# InertiaScreen_CurriculumDesign.net
KiCad netlist of a schematic drawn in Altium Designer
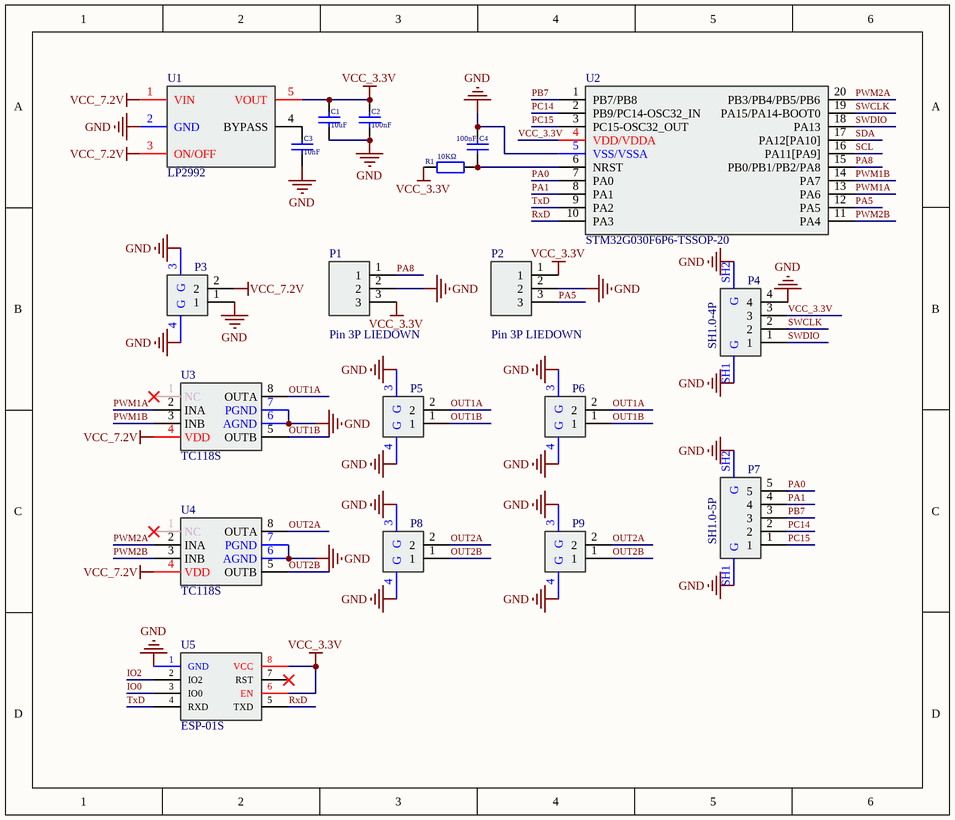
[diagram p0: InertiaScreen_CurriculumDesign.SchDoc]

(export (version "E")
  (design (tool "Eeschema 10.0.6"))
  (components
    (comp (ref "C1")
      (value "10uF")
      (footprint "0402_C")
      (description "贴片电容")
      (libsource (lib "Miscellaneous Devices LC") (part "0402 10uF (106) 20% 6.3V"))
    )
    (comp (ref "C2")
      (value "100nF")
      (footprint "0402_C")
      (description "贴片电容")
      (libsource (lib "Miscellaneous Devices LC") (part "0402 100nF (104) 10% 16V"))
    )
    (comp (ref "C3")
      (value "10nF")
      (footprint "0402_C")
      (description "贴片电容")
      (libsource (lib "Miscellaneous Devices LC") (part "0402 10nF (103) 10% 50V"))
    )
    (comp (ref "C4")
      (value "100nF")
      (footprint "0402_C")
      (description "贴片电容")
      (libsource (lib "Miscellaneous Devices LC") (part "0402 100nF (104) 10% 16V"))
    )
    (comp (ref "P1")
      (value "Pin 3P LIEDOWN")
      (footprint "Pin 3P LieDown")
      (description "排针卧贴 3P")
      (libsource (lib "IntegratedDevices") (part "Pin 3P LIEDOWN"))
    )
    (comp (ref "P2")
      (value "Pin 3P LIEDOWN")
      (footprint "Pin 3P LieDown")
      (description "排针卧贴 3P")
      (libsource (lib "IntegratedDevices") (part "Pin 3P LIEDOWN"))
    )
    (comp (ref "P3")
      (value "SH1.00mm 2P")
      (footprint "SH1.0-2P")
      (description "SH1.00mm 2P 卧贴")
      (libsource (lib "IntegratedDevices") (part "SH1.00mm 2P"))
    )
    (comp (ref "P4")
      (value "SH1.0-4P")
      (footprint "SH1.0-4P")
      (description "SH1.00mm 4P 卧贴")
      (libsource (lib "IntegratedDevices") (part "SH1.0-4P"))
    )
    (comp (ref "P5")
      (value "SH1.00mm 2P")
      (footprint "SH1.0-2P")
      (description "SH1.00mm 2P 卧贴")
      (libsource (lib "IntegratedDevices") (part "SH1.00mm 2P"))
    )
    (comp (ref "P6")
      (value "SH1.00mm 2P")
      (footprint "SH1.0-2P")
      (description "SH1.00mm 2P 卧贴")
      (libsource (lib "IntegratedDevices") (part "SH1.00mm 2P"))
    )
    (comp (ref "P7")
      (value "SH1.0-5P")
      (footprint "SH1.0-5P")
      (description "SH1.00mm 5P 卧贴")
      (libsource (lib "IntegratedDevices") (part "SH1.0-5P"))
    )
    (comp (ref "P8")
      (value "SH1.00mm 2P")
      (footprint "SH1.0-2P")
      (description "SH1.00mm 2P 卧贴")
      (libsource (lib "IntegratedDevices") (part "SH1.00mm 2P"))
    )
    (comp (ref "P9")
      (value "SH1.00mm 2P")
      (footprint "SH1.0-2P")
      (description "SH1.00mm 2P 卧贴")
      (libsource (lib "IntegratedDevices") (part "SH1.00mm 2P"))
    )
    (comp (ref "R1")
      (value "10KΩ")
      (footprint "0402_R")
      (description "贴片电阻")
      (libsource (lib "Miscellaneous Devices LC") (part "0402 10KΩ (1002) 1%"))
    )
    (comp (ref "U1")
      (value "LP2992")
      (footprint "SOT23-5")
      (description "LDO 5.x-3.3V")
      (libsource (lib "IntegratedDevices") (part "LP2992"))
    )
    (comp (ref "U2")
      (value "STM32G030F6P6-TSSOP-20")
      (footprint "TSSOP-20")
      (libsource (lib "IntegratedDevices") (part "STM32G030F6P6-TSSOP-20"))
    )
    (comp (ref "U3")
      (value "TC118S")
      (footprint "SOP-8")
      (description "TC118S FM单路直流电机驱动")
      (libsource (lib "IntegratedDevices") (part "TC118S"))
    )
    (comp (ref "U4")
      (value "TC118S")
      (footprint "SOP-8")
      (description "TC118S FM单路直流电机驱动")
      (libsource (lib "IntegratedDevices") (part "TC118S"))
    )
    (comp (ref "U5")
      (value "ESP-01S")
      (footprint "ESP-01S-NoSlik")
      (description "ESP01S开发板")
      (libsource (lib "IntegratedDevices") (part "ESP-01S"))
    )
  )
  (nets
    (net (code "1") (name "/IO0") (class "Default")
      (node (ref "U5") (pin "3") (pinfunction "IO0_3") (pintype "passive"))
    )
    (net (code "2") (name "/IO2") (class "Default")
      (node (ref "U5") (pin "2") (pinfunction "IO2_2") (pintype "passive"))
    )
    (net (code "3") (name "/OUT1A") (class "Default")
      (node (ref "P5") (pin "2") (pinfunction "2_2") (pintype "passive"))
      (node (ref "P6") (pin "2") (pinfunction "2_2") (pintype "passive"))
      (node (ref "U3") (pin "8") (pinfunction "OUTA_8") (pintype "passive"))
    )
    (net (code "4") (name "/OUT1B") (class "Default")
      (node (ref "P5") (pin "1") (pinfunction "1_1") (pintype "passive"))
      (node (ref "P6") (pin "1") (pinfunction "1_1") (pintype "passive"))
      (node (ref "U3") (pin "5") (pinfunction "OUTB_5") (pintype "passive"))
    )
    (net (code "5") (name "/OUT2A") (class "Default")
      (node (ref "P8") (pin "2") (pinfunction "2_2") (pintype "passive"))
      (node (ref "P9") (pin "2") (pinfunction "2_2") (pintype "passive"))
      (node (ref "U4") (pin "8") (pinfunction "OUTA_8") (pintype "passive"))
    )
    (net (code "6") (name "/OUT2B") (class "Default")
      (node (ref "P8") (pin "1") (pinfunction "1_1") (pintype "passive"))
      (node (ref "P9") (pin "1") (pinfunction "1_1") (pintype "passive"))
      (node (ref "U4") (pin "5") (pinfunction "OUTB_5") (pintype "passive"))
    )
    (net (code "7") (name "/PA0") (class "Default")
      (node (ref "P7") (pin "5") (pinfunction "5_5") (pintype "passive"))
      (node (ref "U2") (pin "7") (pinfunction "PA0_7") (pintype "passive"))
    )
    (net (code "8") (name "/PA1") (class "Default")
      (node (ref "P7") (pin "4") (pinfunction "4_4") (pintype "passive"))
      (node (ref "U2") (pin "8") (pinfunction "PA1_8") (pintype "passive"))
    )
    (net (code "9") (name "/PA5") (class "Default")
      (node (ref "P2") (pin "3") (pinfunction "3_3") (pintype "passive"))
      (node (ref "U2") (pin "12") (pinfunction "PA5_12") (pintype "passive"))
    )
    (net (code "10") (name "/PA8") (class "Default")
      (node (ref "P1") (pin "1") (pinfunction "1_1") (pintype "passive"))
      (node (ref "U2") (pin "15") (pinfunction "PB0/PB1/PB2/PA8_15") (pintype "passive"))
    )
    (net (code "11") (name "/PB7") (class "Default")
      (node (ref "P7") (pin "3") (pinfunction "3_3") (pintype "passive"))
      (node (ref "U2") (pin "1") (pinfunction "PB7/PB8_1") (pintype "passive"))
    )
    (net (code "12") (name "/PC14") (class "Default")
      (node (ref "P7") (pin "2") (pinfunction "2_2") (pintype "passive"))
      (node (ref "U2") (pin "2") (pinfunction "PB9/PC14-OSC32_IN_2") (pintype "passive"))
    )
    (net (code "13") (name "/PC15") (class "Default")
      (node (ref "P7") (pin "1") (pinfunction "1_1") (pintype "passive"))
      (node (ref "U2") (pin "3") (pinfunction "PC15-OSC32_OUT_3") (pintype "passive"))
    )
    (net (code "14") (name "/PWM1A") (class "Default")
      (node (ref "U2") (pin "13") (pinfunction "PA6_13") (pintype "passive"))
      (node (ref "U3") (pin "2") (pinfunction "INA_2") (pintype "passive"))
    )
    (net (code "15") (name "/PWM1B") (class "Default")
      (node (ref "U2") (pin "14") (pinfunction "PA7_14") (pintype "passive"))
      (node (ref "U3") (pin "3") (pinfunction "INB_3") (pintype "passive"))
    )
    (net (code "16") (name "/PWM2A") (class "Default")
      (node (ref "U2") (pin "20") (pinfunction "PB3/PB4/PB5/PB6_20") (pintype "passive"))
      (node (ref "U4") (pin "2") (pinfunction "INA_2") (pintype "passive"))
    )
    (net (code "17") (name "/PWM2B") (class "Default")
      (node (ref "U2") (pin "11") (pinfunction "PA4_11") (pintype "passive"))
      (node (ref "U4") (pin "3") (pinfunction "INB_3") (pintype "passive"))
    )
    (net (code "18") (name "/RxD") (class "Default")
      (node (ref "U2") (pin "10") (pinfunction "PA3_10") (pintype "passive"))
      (node (ref "U5") (pin "5") (pinfunction "TXD_5") (pintype "passive"))
    )
    (net (code "19") (name "/SCL") (class "Default")
      (node (ref "U2") (pin "16") (pinfunction "PA11[PA9]_16") (pintype "passive"))
    )
    (net (code "20") (name "/SDA") (class "Default")
      (node (ref "U2") (pin "17") (pinfunction "PA12[PA10]_17") (pintype "passive"))
    )
    (net (code "21") (name "/SWCLK") (class "Default")
      (node (ref "P4") (pin "2") (pinfunction "2_2") (pintype "passive"))
      (node (ref "U2") (pin "19") (pinfunction "PA15/PA14-BOOT0_19") (pintype "passive"))
    )
    (net (code "22") (name "/SWDIO") (class "Default")
      (node (ref "P4") (pin "1") (pinfunction "1_1") (pintype "passive"))
      (node (ref "U2") (pin "18") (pinfunction "PA13_18") (pintype "passive"))
    )
    (net (code "23") (name "/TxD") (class "Default")
      (node (ref "U2") (pin "9") (pinfunction "PA2_9") (pintype "passive"))
      (node (ref "U5") (pin "4") (pinfunction "RXD_4") (pintype "passive"))
    )
    (net (code "24") (name "GND") (class "Default")
      (node (ref "C1") (pin "1") (pinfunction "1_1") (pintype "passive"))
      (node (ref "C2") (pin "1") (pinfunction "1_1") (pintype "passive"))
      (node (ref "C3") (pin "1") (pinfunction "1_1") (pintype "passive"))
      (node (ref "C4") (pin "2") (pinfunction "2_2") (pintype "passive"))
      (node (ref "P1") (pin "2") (pinfunction "2_2") (pintype "passive"))
      (node (ref "P2") (pin "2") (pinfunction "2_2") (pintype "passive"))
      (node (ref "P3") (pin "1") (pinfunction "1_1") (pintype "passive"))
      (node (ref "P3") (pin "3") (pinfunction "G_3") (pintype "passive"))
      (node (ref "P3") (pin "4") (pinfunction "G_4") (pintype "passive"))
      (node (ref "P4") (pin "4") (pinfunction "4_4") (pintype "passive"))
      (node (ref "P4") (pin "SH1") (pinfunction "G_SH1") (pintype "passive"))
      (node (ref "P4") (pin "SH2") (pinfunction "G_SH2") (pintype "passive"))
      (node (ref "P5") (pin "3") (pinfunction "G_3") (pintype "passive"))
      (node (ref "P5") (pin "4") (pinfunction "G_4") (pintype "passive"))
      (node (ref "P6") (pin "3") (pinfunction "G_3") (pintype "passive"))
      (node (ref "P6") (pin "4") (pinfunction "G_4") (pintype "passive"))
      (node (ref "P7") (pin "SH1") (pinfunction "G_SH1") (pintype "passive"))
      (node (ref "P7") (pin "SH2") (pinfunction "G_SH2") (pintype "passive"))
      (node (ref "P8") (pin "3") (pinfunction "G_3") (pintype "passive"))
      (node (ref "P8") (pin "4") (pinfunction "G_4") (pintype "passive"))
      (node (ref "P9") (pin "3") (pinfunction "G_3") (pintype "passive"))
      (node (ref "P9") (pin "4") (pinfunction "G_4") (pintype "passive"))
      (node (ref "U1") (pin "2") (pinfunction "GND_2") (pintype "passive"))
      (node (ref "U2") (pin "5") (pinfunction "VSS/VSSA_5") (pintype "passive"))
      (node (ref "U3") (pin "6") (pinfunction "AGND_6") (pintype "passive"))
      (node (ref "U3") (pin "7") (pinfunction "PGND_7") (pintype "passive"))
      (node (ref "U4") (pin "6") (pinfunction "AGND_6") (pintype "passive"))
      (node (ref "U4") (pin "7") (pinfunction "PGND_7") (pintype "passive"))
      (node (ref "U5") (pin "1") (pinfunction "GND_1") (pintype "passive"))
    )
    (net (code "25") (name "Net-(U1-BYPASS)") (class "Default")
      (node (ref "C3") (pin "2") (pinfunction "2_2") (pintype "passive"))
      (node (ref "U1") (pin "4") (pinfunction "BYPASS_4") (pintype "passive"))
    )
    (net (code "26") (name "Net-(U2-NRST)") (class "Default")
      (node (ref "C4") (pin "1") (pinfunction "1_1") (pintype "passive"))
      (node (ref "R1") (pin "2") (pinfunction "2_2") (pintype "passive"))
      (node (ref "U2") (pin "6") (pinfunction "NRST_6") (pintype "passive"))
    )
    (net (code "27") (name "VCC_3.3V") (class "Default")
      (node (ref "C1") (pin "2") (pinfunction "2_2") (pintype "passive"))
      (node (ref "C2") (pin "2") (pinfunction "2_2") (pintype "passive"))
      (node (ref "P1") (pin "3") (pinfunction "3_3") (pintype "passive"))
      (node (ref "P2") (pin "1") (pinfunction "1_1") (pintype "passive"))
      (node (ref "P4") (pin "3") (pinfunction "3_3") (pintype "passive"))
      (node (ref "R1") (pin "1") (pinfunction "1_1") (pintype "passive"))
      (node (ref "U1") (pin "5") (pinfunction "VOUT_5") (pintype "passive"))
      (node (ref "U2") (pin "4") (pinfunction "VDD/VDDA_4") (pintype "passive"))
      (node (ref "U5") (pin "6") (pinfunction "EN_6") (pintype "passive"))
      (node (ref "U5") (pin "8") (pinfunction "VCC_8") (pintype "passive"))
    )
    (net (code "28") (name "VCC_7.2V") (class "Default")
      (node (ref "P3") (pin "2") (pinfunction "2_2") (pintype "passive"))
      (node (ref "U1") (pin "1") (pinfunction "VIN_1") (pintype "passive"))
      (node (ref "U1") (pin "3") (pinfunction "ON/OFF_3") (pintype "passive"))
      (node (ref "U3") (pin "4") (pinfunction "VDD_4") (pintype "passive"))
      (node (ref "U4") (pin "4") (pinfunction "VDD_4") (pintype "passive"))
    )
    (net (code "29") (name "unconnected-(U3-NC-Pad1)") (class "Default")
      (node (ref "U3") (pin "1") (pinfunction "NC_1") (pintype "passive+no_connect"))
    )
    (net (code "30") (name "unconnected-(U4-NC-Pad1)") (class "Default")
      (node (ref "U4") (pin "1") (pinfunction "NC_1") (pintype "passive+no_connect"))
    )
    (net (code "31") (name "unconnected-(U5-RST-Pad7)") (class "Default")
      (node (ref "U5") (pin "7") (pinfunction "RST_7") (pintype "passive+no_connect"))
    )
  )
)
